# rs485_interface.net
KiCad netlist of a schematic drawn in Altium Designer
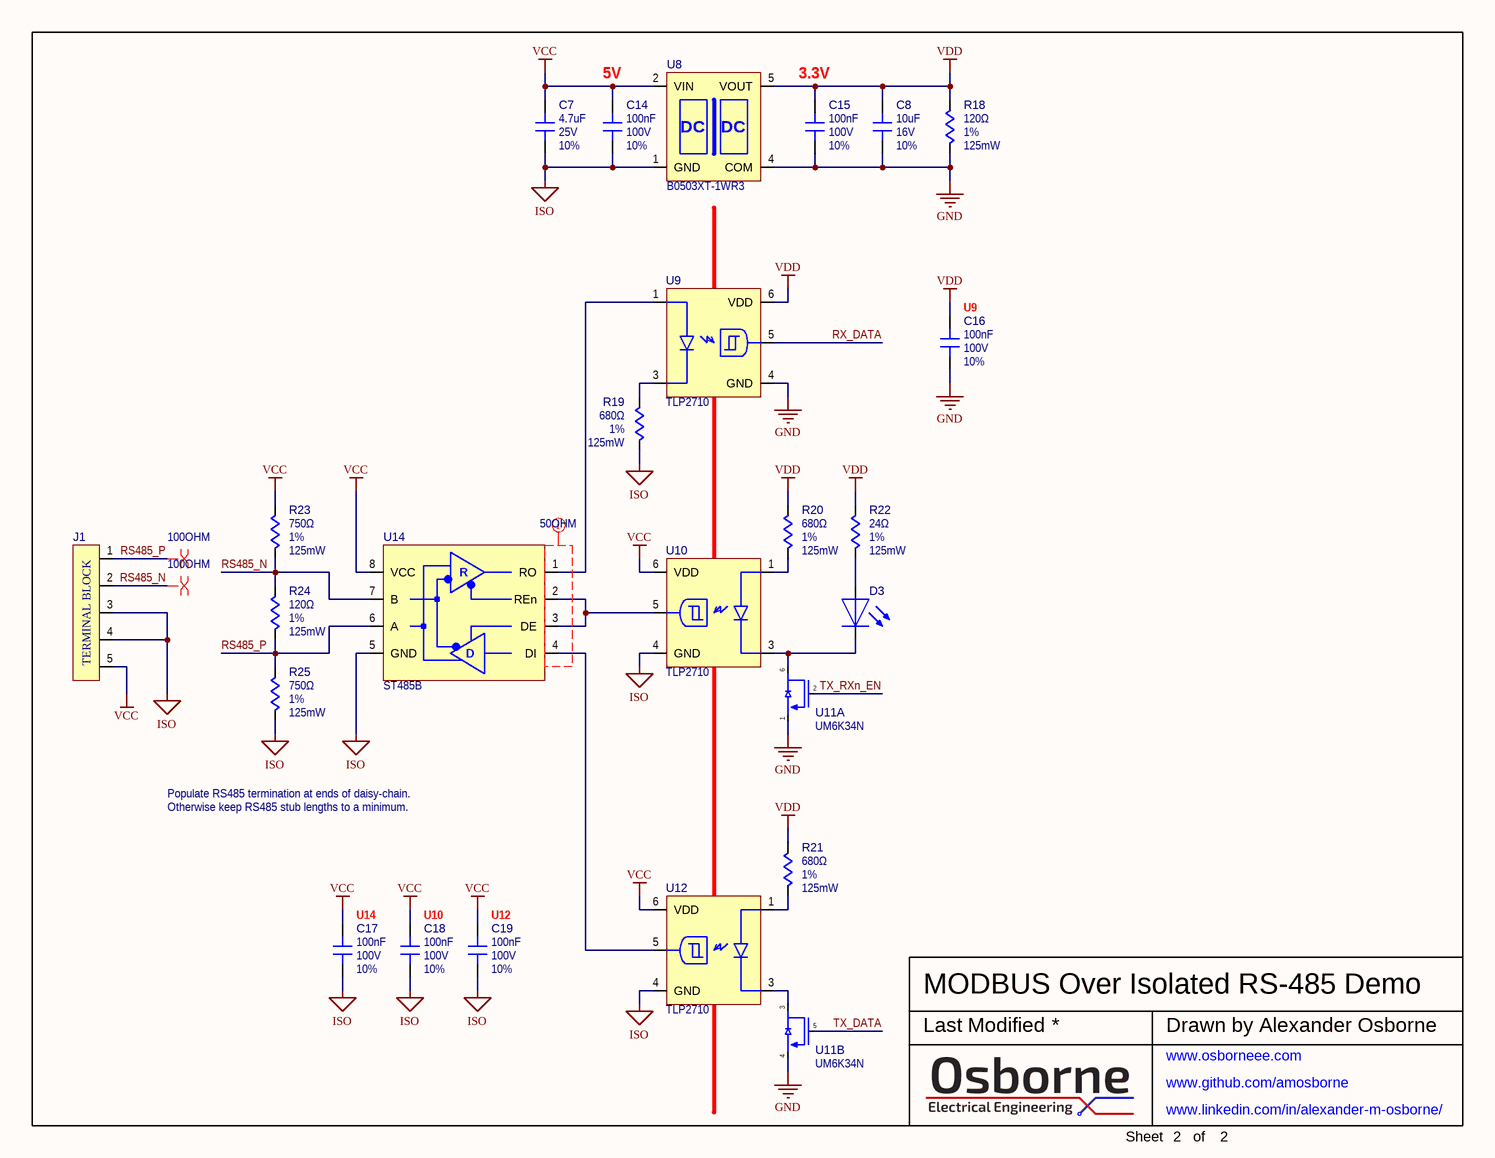
[diagram p0: rs485_interface.SchDoc]

(export (version "E")
  (design (tool "Eeschema 10.0.6"))
  (components
    (comp (ref "C7")
      (value "4.7uF")
      (footprint "C0805")
      (description "CAP, CER, 4.7uF ±10%, 25V, 0805")
      (fields
        (field (name "VOLTAGE") "25V")
        (field (name "TOLERANCE") "10%")
        (field (name "Comment") "CAP-CER-4U70-10T-25V-0805")
      )
      (libsource (lib "schematic_library") (part "CAP-CER-4U70-10T-25V-0805"))
    )
    (comp (ref "C8")
      (value "10uF")
      (footprint "C0805")
      (description "CAP, CER, 10uF ±10%, 16V, 0805")
      (fields
        (field (name "VOLTAGE") "16V")
        (field (name "TOLERANCE") "10%")
        (field (name "Comment") "CAP-CER-10U0-10T-16V-0805")
      )
      (libsource (lib "schematic_library") (part "CAP-CER-10U0-10T-16V-0805"))
    )
    (comp (ref "C14")
      (value "100nF")
      (footprint "C0805")
      (description "CAP, CER, 100nF ±10%, 100V, 0805")
      (fields
        (field (name "VOLTAGE") "100V")
        (field (name "TOLERANCE") "10%")
        (field (name "Comment") "CAP-CER-100N-10T-100V-0805")
      )
      (libsource (lib "schematic_library") (part "CAP-CER-100N-10T-100V-0805"))
    )
    (comp (ref "C15")
      (value "100nF")
      (footprint "C0805")
      (description "CAP, CER, 100nF ±10%, 100V, 0805")
      (fields
        (field (name "VOLTAGE") "100V")
        (field (name "TOLERANCE") "10%")
        (field (name "Comment") "CAP-CER-100N-10T-100V-0805")
      )
      (libsource (lib "schematic_library") (part "CAP-CER-100N-10T-100V-0805"))
    )
    (comp (ref "C16")
      (value "100nF")
      (footprint "C0805")
      (description "CAP, CER, 100nF ±10%, 100V, 0805")
      (fields
        (field (name "VOLTAGE") "100V")
        (field (name "TOLERANCE") "10%")
        (field (name "Comment") "CAP-CER-100N-10T-100V-0805")
      )
      (libsource (lib "schematic_library") (part "CAP-CER-100N-10T-100V-0805"))
    )
    (comp (ref "C17")
      (value "100nF")
      (footprint "C0805")
      (description "CAP, CER, 100nF ±10%, 100V, 0805")
      (fields
        (field (name "VOLTAGE") "100V")
        (field (name "TOLERANCE") "10%")
        (field (name "Comment") "CAP-CER-100N-10T-100V-0805")
      )
      (libsource (lib "schematic_library") (part "CAP-CER-100N-10T-100V-0805"))
    )
    (comp (ref "C18")
      (value "100nF")
      (footprint "C0805")
      (description "CAP, CER, 100nF ±10%, 100V, 0805")
      (fields
        (field (name "VOLTAGE") "100V")
        (field (name "TOLERANCE") "10%")
        (field (name "Comment") "CAP-CER-100N-10T-100V-0805")
      )
      (libsource (lib "schematic_library") (part "CAP-CER-100N-10T-100V-0805"))
    )
    (comp (ref "C19")
      (value "100nF")
      (footprint "C0805")
      (description "CAP, CER, 100nF ±10%, 100V, 0805")
      (fields
        (field (name "VOLTAGE") "100V")
        (field (name "TOLERANCE") "10%")
        (field (name "Comment") "CAP-CER-100N-10T-100V-0805")
      )
      (libsource (lib "schematic_library") (part "CAP-CER-100N-10T-100V-0805"))
    )
    (comp (ref "D3")
      (value "LED_BLUE")
      (footprint "D0805")
      (description "Blue LED Indicator 0805")
      (libsource (lib "schematic_library") (part "LED_BLUE"))
    )
    (comp (ref "J1")
      (value "TBLOCK_5POS")
      (footprint "TBLOCK_5POS")
      (description "Screw Terminal Block, 5-Position")
      (libsource (lib "schematic_library") (part "TBLOCK_5POS"))
    )
    (comp (ref "R18")
      (value "120Ω")
      (footprint "R0805")
      (description "RES, 120Ω ±1.00%, 125mW, 0805")
      (fields
        (field (name "TOLERANCE") "1%")
        (field (name "POWER") "125mW")
        (field (name "Comment") "RES-120R-1T00-W125-0805")
      )
      (libsource (lib "schematic_library") (part "RES-120R-1T00-W125-0805"))
    )
    (comp (ref "R19")
      (value "680Ω")
      (footprint "R0805")
      (description "RES, 680Ω ±1.00%, 125mW, 0805")
      (fields
        (field (name "TOLERANCE") "1%")
        (field (name "POWER") "125mW")
        (field (name "Comment") "RES-680R-1T00-W125-0805")
      )
      (libsource (lib "schematic_library") (part "RES-680R-1T00-W125-0805"))
    )
    (comp (ref "R20")
      (value "680Ω")
      (footprint "R0805")
      (description "RES, 680Ω ±1.00%, 125mW, 0805")
      (fields
        (field (name "TOLERANCE") "1%")
        (field (name "POWER") "125mW")
        (field (name "Comment") "RES-680R-1T00-W125-0805")
      )
      (libsource (lib "schematic_library") (part "RES-680R-1T00-W125-0805"))
    )
    (comp (ref "R21")
      (value "680Ω")
      (footprint "R0805")
      (description "RES, 680Ω ±1.00%, 125mW, 0805")
      (fields
        (field (name "TOLERANCE") "1%")
        (field (name "POWER") "125mW")
        (field (name "Comment") "RES-680R-1T00-W125-0805")
      )
      (libsource (lib "schematic_library") (part "RES-680R-1T00-W125-0805"))
    )
    (comp (ref "R22")
      (value "24Ω")
      (footprint "R0805")
      (description "RES, 24Ω ±1.00%, 125mW, 0805")
      (fields
        (field (name "TOLERANCE") "1%")
        (field (name "POWER") "125mW")
        (field (name "Comment") "RES-24R0-1T00-W125-0805")
      )
      (libsource (lib "schematic_library") (part "RES-24R0-1T00-W125-0805"))
    )
    (comp (ref "R23")
      (value "750Ω")
      (footprint "R0805")
      (description "RES, 750Ω ±1.00%, 125mW, 0805")
      (fields
        (field (name "TOLERANCE") "1%")
        (field (name "POWER") "125mW")
        (field (name "Comment") "RES-750R-1T00-W125-0805")
      )
      (libsource (lib "schematic_library") (part "RES-750R-1T00-W125-0805"))
    )
    (comp (ref "R24")
      (value "120Ω")
      (footprint "R0805")
      (description "RES, 120Ω ±1.00%, 125mW, 0805")
      (fields
        (field (name "TOLERANCE") "1%")
        (field (name "POWER") "125mW")
        (field (name "Comment") "RES-120R-1T00-W125-0805")
      )
      (libsource (lib "schematic_library") (part "RES-120R-1T00-W125-0805"))
    )
    (comp (ref "R25")
      (value "750Ω")
      (footprint "R0805")
      (description "RES, 750Ω ±1.00%, 125mW, 0805")
      (fields
        (field (name "TOLERANCE") "1%")
        (field (name "POWER") "125mW")
        (field (name "Comment") "RES-750R-1T00-W125-0805")
      )
      (libsource (lib "schematic_library") (part "RES-750R-1T00-W125-0805"))
    )
    (comp (ref "U8")
      (value "B0503XT-1WR3")
      (footprint "B05_XT-1WR3")
      (description "Isolated DC/DC, 5Vin, 3.3Vout, 300mA")
      (libsource (lib "schematic_library") (part "B0503XT-1WR3"))
    )
    (comp (ref "U9")
      (value "TLP2710")
      (footprint "TLP2710_SO-6L")
      (description "Logic Output Optoisolator 5MBd")
      (libsource (lib "schematic_library") (part "TLP2710"))
    )
    (comp (ref "U10")
      (value "TLP2710")
      (footprint "TLP2710_SO-6L")
      (description "Logic Output Optoisolator 5MBd")
      (libsource (lib "") (part "TLP2710_1"))
    )
    (comp (ref "U11")
      (value "UM6K34N")
      (footprint "UM6K34N_SC-88")
      (description "NCH+NCH 50V 200mA Small Signal MOSFET")
      (libsource (lib "schematic_library") (part "UM6K34N"))
    )
    (comp (ref "U12")
      (value "TLP2710")
      (footprint "TLP2710_SO-6L")
      (description "Logic Output Optoisolator 5MBd")
      (libsource (lib "") (part "TLP2710_1"))
    )
    (comp (ref "U14")
      (value "ST485B")
      (footprint "ST485B_SO-8")
      (description "1/1 RS485 Transceiver, Half-Duplex")
      (libsource (lib "schematic_library") (part "ST485B"))
    )
  )
  (nets
    (net (code "1") (name "/RS485_N") (class "Default")
      (node (ref "J1") (pin "2") (pintype "passive"))
      (node (ref "R23") (pin "2") (pintype "passive"))
      (node (ref "R24") (pin "1") (pintype "passive"))
      (node (ref "U14") (pin "7") (pinfunction "B_7") (pintype "passive"))
    )
    (net (code "2") (name "/RS485_P") (class "Default")
      (node (ref "J1") (pin "1") (pintype "passive"))
      (node (ref "R24") (pin "2") (pintype "passive"))
      (node (ref "R25") (pin "1") (pintype "passive"))
      (node (ref "U14") (pin "6") (pinfunction "A_6") (pintype "passive"))
    )
    (net (code "3") (name "/RX_DATA") (class "Default")
      (node (ref "U9") (pin "5") (pinfunction "VO_5") (pintype "passive"))
    )
    (net (code "4") (name "/TX_DATA") (class "Default")
      (node (ref "U11") (pin "5") (pinfunction "G2_5") (pintype "passive"))
    )
    (net (code "5") (name "/TX_RXn_EN") (class "Default")
      (node (ref "U11") (pin "2") (pinfunction "G1_2") (pintype "passive"))
    )
    (net (code "6") (name "GND") (class "Default")
      (node (ref "C15") (pin "2") (pintype "passive"))
      (node (ref "C16") (pin "2") (pintype "passive"))
      (node (ref "C8") (pin "2") (pintype "passive"))
      (node (ref "R18") (pin "2") (pintype "passive"))
      (node (ref "U11") (pin "1") (pinfunction "S1_1") (pintype "passive"))
      (node (ref "U11") (pin "4") (pinfunction "S2_4") (pintype "passive"))
      (node (ref "U8") (pin "4") (pinfunction "COM_4") (pintype "passive"))
      (node (ref "U9") (pin "4") (pinfunction "GND_4") (pintype "passive"))
    )
    (net (code "7") (name "ISO") (class "Default")
      (node (ref "C14") (pin "2") (pintype "passive"))
      (node (ref "C17") (pin "2") (pintype "passive"))
      (node (ref "C18") (pin "2") (pintype "passive"))
      (node (ref "C19") (pin "2") (pintype "passive"))
      (node (ref "C7") (pin "2") (pintype "passive"))
      (node (ref "J1") (pin "3") (pintype "passive"))
      (node (ref "J1") (pin "4") (pintype "passive"))
      (node (ref "R19") (pin "2") (pintype "passive"))
      (node (ref "R25") (pin "2") (pintype "passive"))
      (node (ref "U10") (pin "4") (pinfunction "GND_4") (pintype "passive"))
      (node (ref "U12") (pin "4") (pinfunction "GND_4") (pintype "passive"))
      (node (ref "U14") (pin "5") (pinfunction "GND_5") (pintype "passive"))
      (node (ref "U8") (pin "1") (pinfunction "GND_1") (pintype "passive"))
    )
    (net (code "8") (name "Net-(D3-Pad2)") (class "Default")
      (node (ref "D3") (pin "2") (pinfunction "2_2") (pintype "passive"))
      (node (ref "R22") (pin "2") (pintype "passive"))
    )
    (net (code "9") (name "Net-(U9-CATHODE)") (class "Default")
      (node (ref "R19") (pin "1") (pintype "passive"))
      (node (ref "U9") (pin "3") (pinfunction "CATHODE_3") (pintype "passive"))
    )
    (net (code "10") (name "Net-(U10-ANODE)") (class "Default")
      (node (ref "R20") (pin "2") (pintype "passive"))
      (node (ref "U10") (pin "1") (pinfunction "ANODE_1") (pintype "passive"))
    )
    (net (code "11") (name "Net-(U10-CATHODE)") (class "Default")
      (node (ref "D3") (pin "1") (pinfunction "1_1") (pintype "passive"))
      (node (ref "U10") (pin "3") (pinfunction "CATHODE_3") (pintype "passive"))
      (node (ref "U11") (pin "6") (pinfunction "D1_6") (pintype "passive"))
    )
    (net (code "12") (name "Net-(U10-VO)") (class "Default")
      (node (ref "U10") (pin "5") (pinfunction "VO_5") (pintype "passive"))
      (node (ref "U14") (pin "2") (pinfunction "REn_2") (pintype "passive"))
      (node (ref "U14") (pin "3") (pinfunction "DE_3") (pintype "passive"))
    )
    (net (code "13") (name "Net-(U11B-D2)") (class "Default")
      (node (ref "U11") (pin "3") (pinfunction "D2_3") (pintype "passive"))
      (node (ref "U12") (pin "3") (pinfunction "CATHODE_3") (pintype "passive"))
    )
    (net (code "14") (name "Net-(U12-ANODE)") (class "Default")
      (node (ref "R21") (pin "2") (pintype "passive"))
      (node (ref "U12") (pin "1") (pinfunction "ANODE_1") (pintype "passive"))
    )
    (net (code "15") (name "Net-(U12-VO)") (class "Default")
      (node (ref "U12") (pin "5") (pinfunction "VO_5") (pintype "passive"))
      (node (ref "U14") (pin "4") (pinfunction "DI_4") (pintype "passive"))
    )
    (net (code "16") (name "Net-(U14-RO)") (class "Default")
      (node (ref "U14") (pin "1") (pinfunction "RO_1") (pintype "passive"))
      (node (ref "U9") (pin "1") (pinfunction "ANODE_1") (pintype "passive"))
    )
    (net (code "17") (name "VCC") (class "Default")
      (node (ref "C14") (pin "1") (pintype "passive"))
      (node (ref "C17") (pin "1") (pintype "passive"))
      (node (ref "C18") (pin "1") (pintype "passive"))
      (node (ref "C19") (pin "1") (pintype "passive"))
      (node (ref "C7") (pin "1") (pintype "passive"))
      (node (ref "J1") (pin "5") (pintype "passive"))
      (node (ref "R23") (pin "1") (pintype "passive"))
      (node (ref "U10") (pin "6") (pinfunction "VDD_6") (pintype "passive"))
      (node (ref "U12") (pin "6") (pinfunction "VDD_6") (pintype "passive"))
      (node (ref "U14") (pin "8") (pinfunction "VCC_8") (pintype "passive"))
      (node (ref "U8") (pin "2") (pinfunction "VIN_2") (pintype "passive"))
    )
    (net (code "18") (name "VDD") (class "Default")
      (node (ref "C15") (pin "1") (pintype "passive"))
      (node (ref "C16") (pin "1") (pintype "passive"))
      (node (ref "C8") (pin "1") (pintype "passive"))
      (node (ref "R18") (pin "1") (pintype "passive"))
      (node (ref "R20") (pin "1") (pintype "passive"))
      (node (ref "R21") (pin "1") (pintype "passive"))
      (node (ref "R22") (pin "1") (pintype "passive"))
      (node (ref "U8") (pin "5") (pinfunction "VOUT_5") (pintype "passive"))
      (node (ref "U9") (pin "6") (pinfunction "VDD_6") (pintype "passive"))
    )
    (net (code "19") (name "unconnected-(U8-NC-Pad8)") (class "Default")
      (node (ref "U8") (pin "8") (pinfunction "NC_8") (pintype "passive"))
    )
    (net (code "20") (name "unconnected-(U9-NC-Pad2)") (class "Default")
      (node (ref "U9") (pin "2") (pinfunction "NC_2") (pintype "passive"))
    )
    (net (code "21") (name "unconnected-(U10-NC-Pad2)") (class "Default")
      (node (ref "U10") (pin "2") (pinfunction "NC_2") (pintype "passive"))
    )
    (net (code "22") (name "unconnected-(U12-NC-Pad2)") (class "Default")
      (node (ref "U12") (pin "2") (pinfunction "NC_2") (pintype "passive"))
    )
  )
)
